# Voicecard-SVF-v0_7.net
KiCad netlist of a schematic drawn in EAGLE
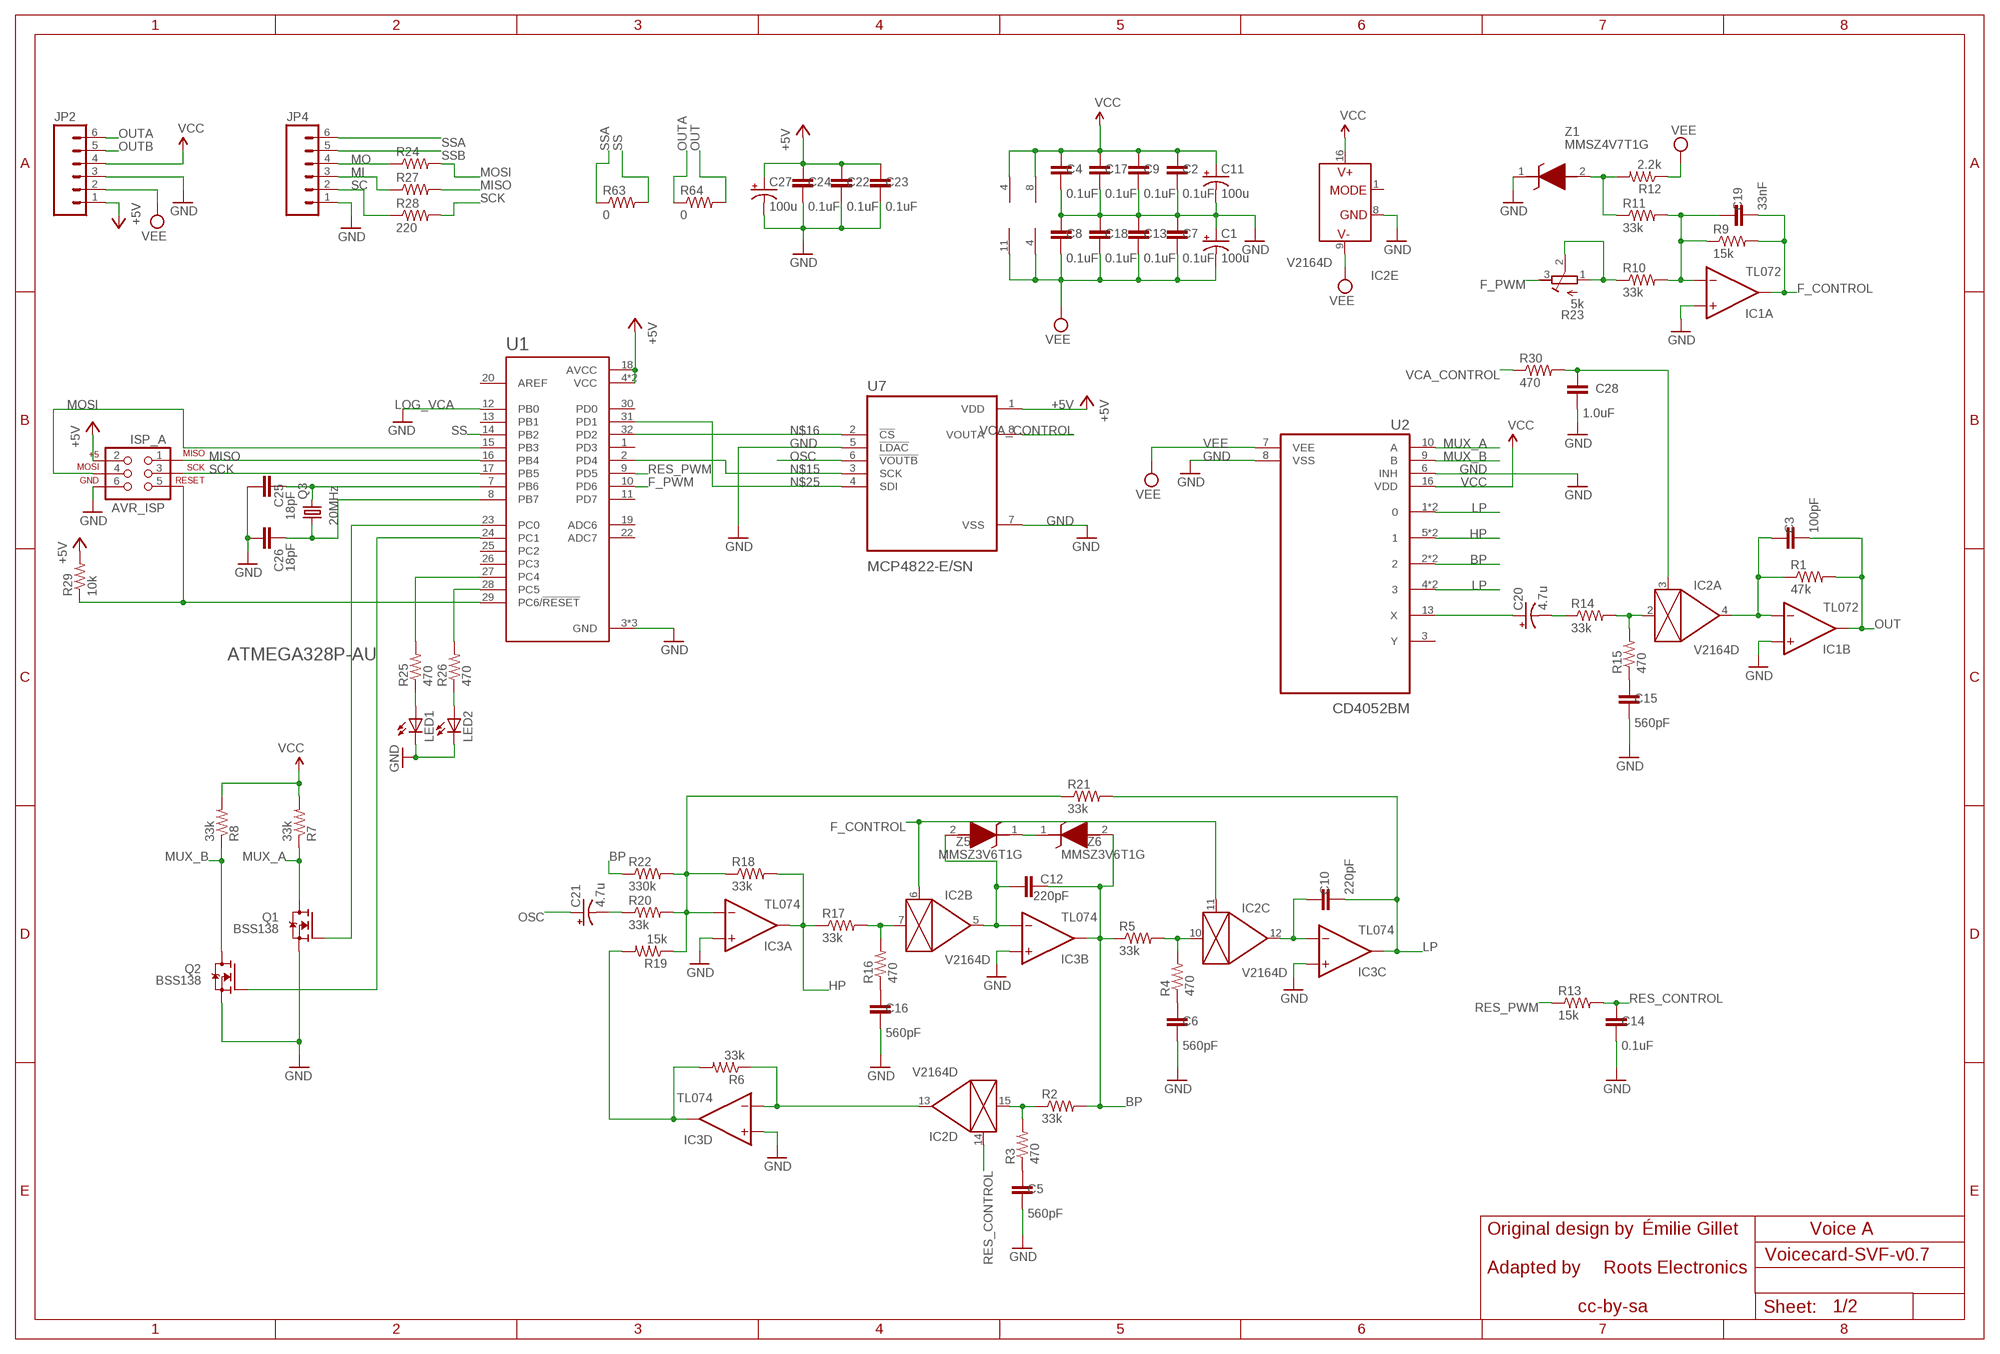
[diagram p0: schematic, sheet 1]
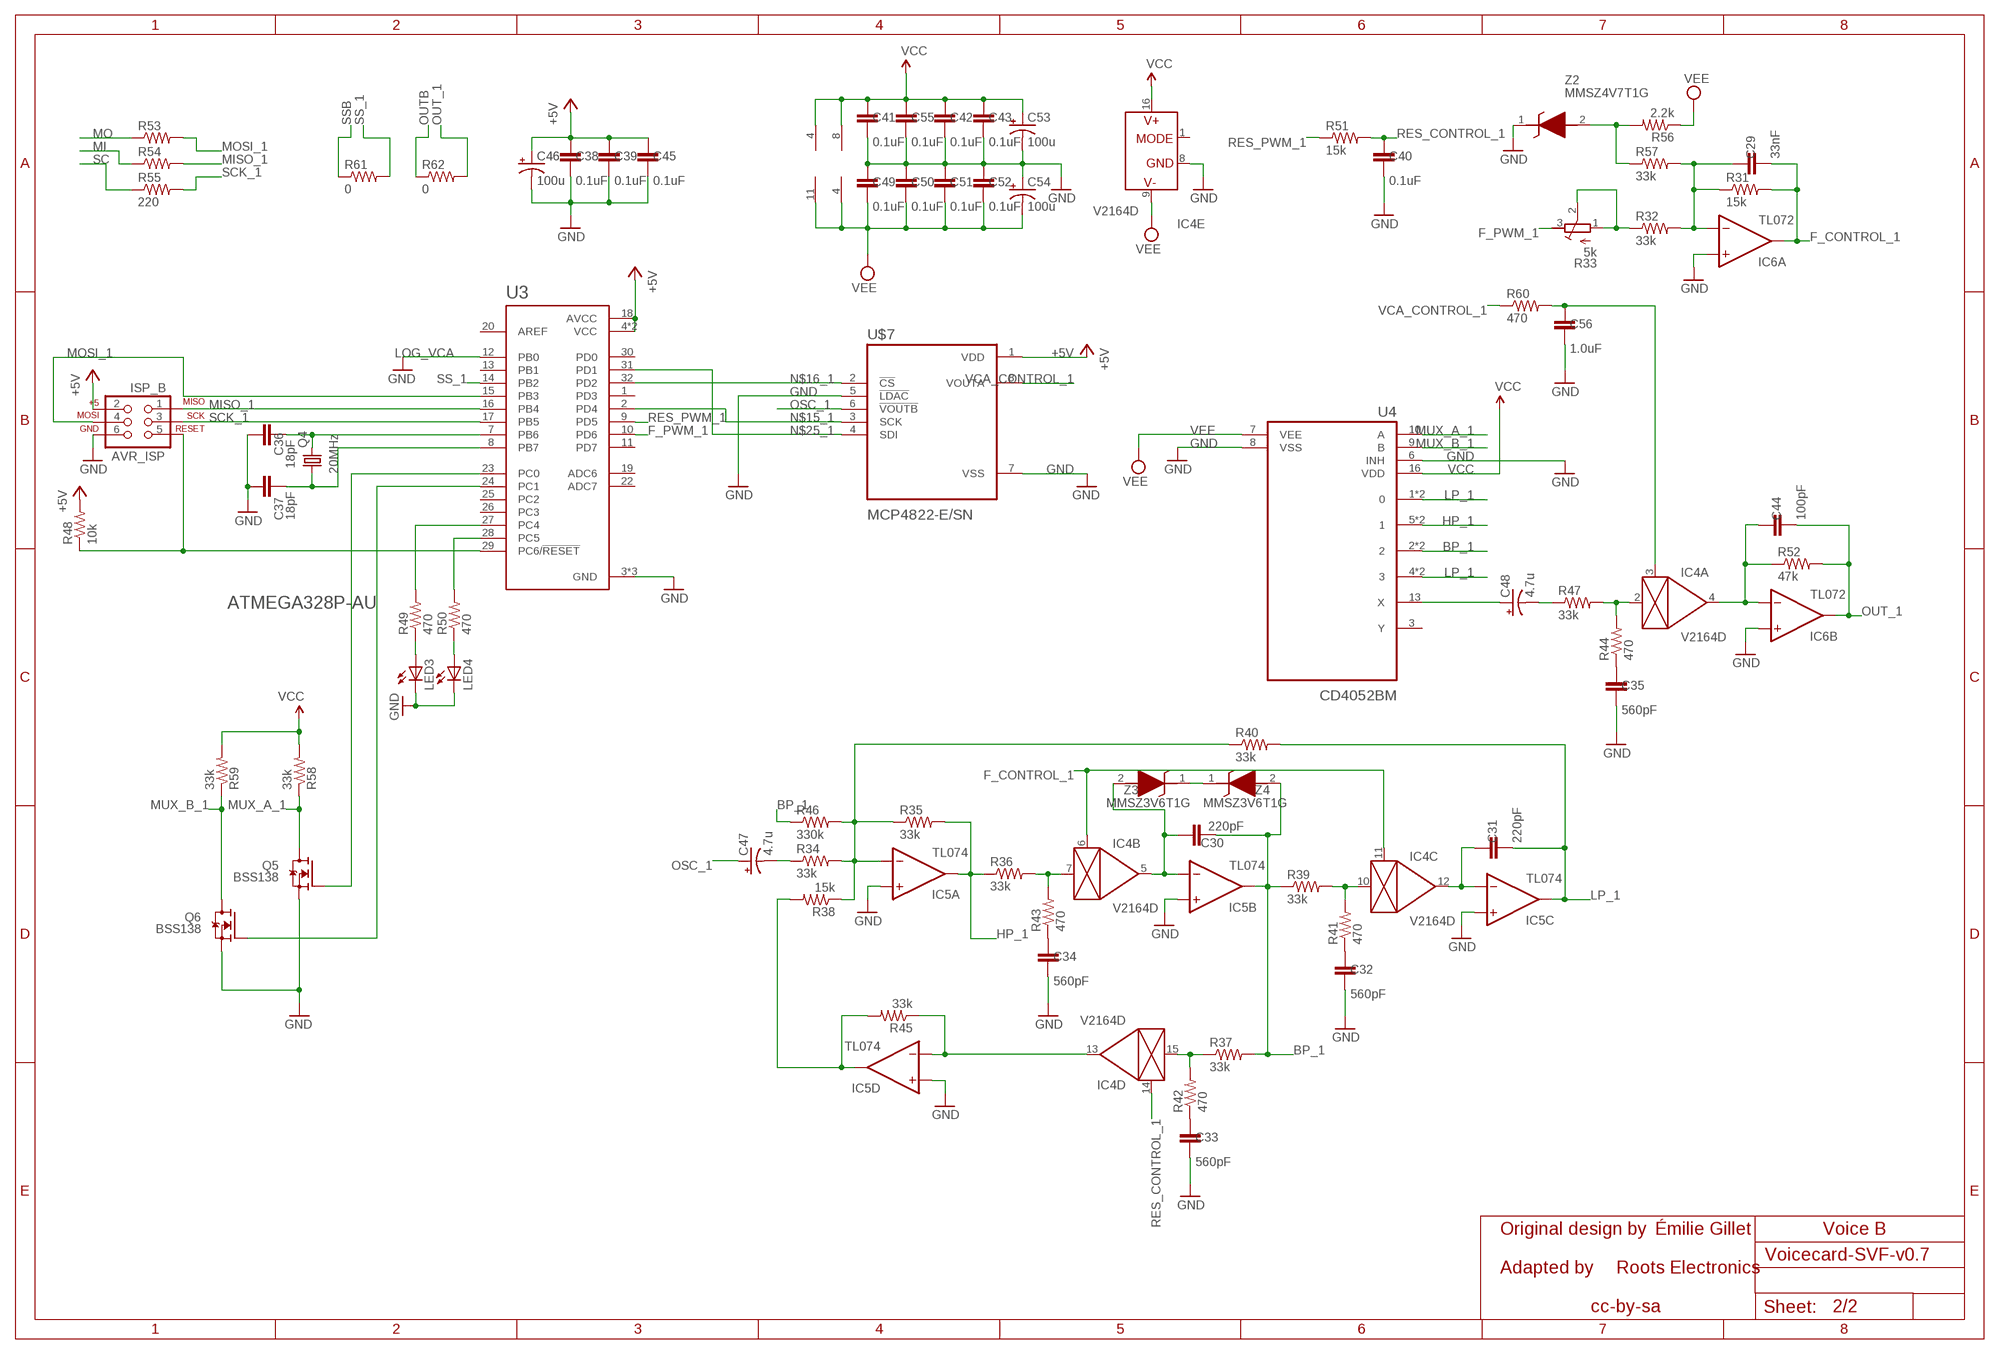
[diagram p1: schematic, sheet 2]

(export (version "E")
  (design (tool "Eeschema 10.0.6"))
  (components
    (comp (ref "C29")
      (value "33nF")
      (footprint "eagle-import:0603")
      (libsource (lib "eagle-import") (part "33NF-0603-50V-10%"))
    )
    (comp (ref "C30")
      (value "220pF")
      (footprint "eagle-import:0603")
      (libsource (lib "eagle-import") (part "270PF-0603-50V-5%"))
    )
    (comp (ref "C31")
      (value "220pF")
      (footprint "eagle-import:0603")
      (libsource (lib "eagle-import") (part "270PF-0603-50V-5%"))
    )
    (comp (ref "C32")
      (value "560pF")
      (footprint "eagle-import:0603")
      (libsource (lib "eagle-import") (part "560PF-0603-50V-5%"))
    )
    (comp (ref "C33")
      (value "560pF")
      (footprint "eagle-import:0603")
      (libsource (lib "eagle-import") (part "560PF-0603-50V-5%"))
    )
    (comp (ref "C34")
      (value "560pF")
      (footprint "eagle-import:0603")
      (libsource (lib "eagle-import") (part "560PF-0603-50V-5%"))
    )
    (comp (ref "C35")
      (value "560pF")
      (footprint "eagle-import:0603")
      (libsource (lib "eagle-import") (part "560PF-0603-50V-5%"))
    )
    (comp (ref "C36")
      (value "18pF")
      (footprint "eagle-import:0603")
      (libsource (lib "eagle-import") (part "18PF-0603-50V-5%"))
    )
    (comp (ref "C37")
      (value "18pF")
      (footprint "eagle-import:0603")
      (libsource (lib "eagle-import") (part "18PF-0603-50V-5%"))
    )
    (comp (ref "C38")
      (value "0.1uF")
      (footprint "eagle-import:0603")
      (libsource (lib "eagle-import") (part "0.1UF-0603-25V-5%"))
    )
    (comp (ref "C39")
      (value "0.1uF")
      (footprint "eagle-import:0603")
      (libsource (lib "eagle-import") (part "0.1UF-0603-25V-5%"))
    )
    (comp (ref "C40")
      (value "0.1uF")
      (footprint "eagle-import:0603")
      (libsource (lib "eagle-import") (part "0.1UF-0603-25V-5%"))
    )
    (comp (ref "C41")
      (value "0.1uF")
      (footprint "eagle-import:0603")
      (libsource (lib "eagle-import") (part "0.1UF-0603-25V-5%"))
    )
    (comp (ref "C42")
      (value "0.1uF")
      (footprint "eagle-import:0603")
      (libsource (lib "eagle-import") (part "0.1UF-0603-25V-5%"))
    )
    (comp (ref "C43")
      (value "0.1uF")
      (footprint "eagle-import:0603")
      (libsource (lib "eagle-import") (part "0.1UF-0603-25V-5%"))
    )
    (comp (ref "C44")
      (value "100pF")
      (footprint "eagle-import:0603")
      (libsource (lib "eagle-import") (part "100PF-0603-50V-5%"))
    )
    (comp (ref "C45")
      (value "0.1uF")
      (footprint "eagle-import:0603")
      (libsource (lib "eagle-import") (part "0.1UF-0603-25V-5%"))
    )
    (comp (ref "C46")
      (value "100u")
      (footprint "eagle-import:PANASONIC_C")
      (libsource (lib "eagle-import") (part "CPOL-USC"))
    )
    (comp (ref "C47")
      (value "4.7u")
      (footprint "eagle-import:PANASONIC_A")
      (libsource (lib "eagle-import") (part "CPOL-USA"))
    )
    (comp (ref "C48")
      (value "4.7u")
      (footprint "eagle-import:PANASONIC_A")
      (libsource (lib "eagle-import") (part "CPOL-USA"))
    )
    (comp (ref "C49")
      (value "0.1uF")
      (footprint "eagle-import:0603")
      (libsource (lib "eagle-import") (part "0.1UF-0603-25V-5%"))
    )
    (comp (ref "C50")
      (value "0.1uF")
      (footprint "eagle-import:0603")
      (libsource (lib "eagle-import") (part "0.1UF-0603-25V-5%"))
    )
    (comp (ref "C51")
      (value "0.1uF")
      (footprint "eagle-import:0603")
      (libsource (lib "eagle-import") (part "0.1UF-0603-25V-5%"))
    )
    (comp (ref "C52")
      (value "0.1uF")
      (footprint "eagle-import:0603")
      (libsource (lib "eagle-import") (part "0.1UF-0603-25V-5%"))
    )
    (comp (ref "C53")
      (value "100u")
      (footprint "eagle-import:PANASONIC_C")
      (libsource (lib "eagle-import") (part "CPOL-USC"))
    )
    (comp (ref "C54")
      (value "100u")
      (footprint "eagle-import:PANASONIC_C")
      (libsource (lib "eagle-import") (part "CPOL-USC"))
    )
    (comp (ref "C55")
      (value "0.1uF")
      (footprint "eagle-import:0603")
      (libsource (lib "eagle-import") (part "0.1UF-0603-25V-5%"))
    )
    (comp (ref "C56")
      (value "1.0uF")
      (footprint "eagle-import:0603")
      (libsource (lib "eagle-import") (part "1.0UF-0603-16V-10%"))
    )
    (comp (ref "IC4")
      (value "V2164D")
      (footprint "eagle-import:SOIC16N")
      (libsource (lib "eagle-import") (part "SSM2164S"))
    )
    (comp (ref "IC5")
      (value "TL074")
      (footprint "eagle-import:SO14")
      (libsource (lib "eagle-import") (part "TL074_SMD"))
    )
    (comp (ref "IC6")
      (value "TL072")
      (footprint "eagle-import:SO08")
      (libsource (lib "eagle-import") (part "TL072_SMD"))
    )
    (comp (ref "ISP_B")
      (value "AVR_ISP")
      (footprint "eagle-import:2X3")
      (libsource (lib "eagle-import") (part "AVR_SPI_PRG_6PTH"))
    )
    (comp (ref "LED3")
      (value "LED3MM")
      (footprint "eagle-import:LED3MM")
      (libsource (lib "eagle-import") (part "LED3MM"))
    )
    (comp (ref "LED4")
      (value "LED3MM")
      (footprint "eagle-import:LED3MM")
      (libsource (lib "eagle-import") (part "LED3MM"))
    )
    (comp (ref "Q4")
      (value "20MHz")
      (footprint "eagle-import:HC49UP")
      (libsource (lib "eagle-import") (part "CRYSTALHC49UP"))
    )
    (comp (ref "Q5")
      (value "BSS138")
      (footprint "eagle-import:SOT95P240X111-3N")
      (fields (field (name "MF") "ON Semiconductor"))
      (libsource (lib "eagle-import") (part "BSS138"))
    )
    (comp (ref "Q6")
      (value "BSS138")
      (footprint "eagle-import:SOT95P240X111-3N")
      (fields (field (name "MF") "ON Semiconductor"))
      (libsource (lib "eagle-import") (part "BSS138"))
    )
    (comp (ref "R31")
      (value "15k")
      (footprint "eagle-import:0603")
      (libsource (lib "eagle-import") (part "15KOHM-0603-1/10W-1%"))
    )
    (comp (ref "R32")
      (value "33k")
      (footprint "eagle-import:0603")
      (libsource (lib "eagle-import") (part "33KOHM-0603-1/10W-1%"))
    )
    (comp (ref "R33")
      (value "5k")
      (footprint "eagle-import:RTRIM3296P")
      (libsource (lib "eagle-import") (part "R-TRIMM3296P"))
    )
    (comp (ref "R34")
      (value "33k")
      (footprint "eagle-import:0603")
      (libsource (lib "eagle-import") (part "33KOHM-0603-1/10W-1%"))
    )
    (comp (ref "R35")
      (value "33k")
      (footprint "eagle-import:0603")
      (libsource (lib "eagle-import") (part "33KOHM-0603-1/10W-1%"))
    )
    (comp (ref "R36")
      (value "33k")
      (footprint "eagle-import:0603")
      (libsource (lib "eagle-import") (part "33KOHM-0603-1/10W-1%"))
    )
    (comp (ref "R37")
      (value "33k")
      (footprint "eagle-import:0603")
      (libsource (lib "eagle-import") (part "33KOHM-0603-1/10W-1%"))
    )
    (comp (ref "R38")
      (value "15k")
      (footprint "eagle-import:0603")
      (libsource (lib "eagle-import") (part "15KOHM-0603-1/10W-1%"))
    )
    (comp (ref "R39")
      (value "33k")
      (footprint "eagle-import:0603")
      (libsource (lib "eagle-import") (part "33KOHM-0603-1/10W-1%"))
    )
    (comp (ref "R40")
      (value "33k")
      (footprint "eagle-import:0603")
      (libsource (lib "eagle-import") (part "33KOHM-0603-1/10W-1%"))
    )
    (comp (ref "R41")
      (value "470")
      (footprint "eagle-import:0603")
      (libsource (lib "eagle-import") (part "470OHM-0603-1/10W-1%"))
    )
    (comp (ref "R42")
      (value "470")
      (footprint "eagle-import:0603")
      (libsource (lib "eagle-import") (part "470OHM-0603-1/10W-1%"))
    )
    (comp (ref "R43")
      (value "470")
      (footprint "eagle-import:0603")
      (libsource (lib "eagle-import") (part "470OHM-0603-1/10W-1%"))
    )
    (comp (ref "R44")
      (value "470")
      (footprint "eagle-import:0603")
      (libsource (lib "eagle-import") (part "470OHM-0603-1/10W-1%"))
    )
    (comp (ref "R45")
      (value "33k")
      (footprint "eagle-import:0603")
      (libsource (lib "eagle-import") (part "33KOHM-0603-1/10W-1%"))
    )
    (comp (ref "R46")
      (value "330k")
      (footprint "eagle-import:0603")
      (libsource (lib "eagle-import") (part "330KOHM-0603-1/10W-1%"))
    )
    (comp (ref "R47")
      (value "33k")
      (footprint "eagle-import:0603")
      (libsource (lib "eagle-import") (part "33KOHM-0603-1/10W-1%"))
    )
    (comp (ref "R48")
      (value "10k")
      (footprint "eagle-import:0603")
      (libsource (lib "eagle-import") (part "10KOHM-0603-1/10W-1%"))
    )
    (comp (ref "R49")
      (value "470")
      (footprint "eagle-import:0603")
      (libsource (lib "eagle-import") (part "470OHM-0603-1/10W-1%"))
    )
    (comp (ref "R50")
      (value "470")
      (footprint "eagle-import:0603")
      (libsource (lib "eagle-import") (part "470OHM-0603-1/10W-1%"))
    )
    (comp (ref "R51")
      (value "15k")
      (footprint "eagle-import:0603")
      (libsource (lib "eagle-import") (part "15KOHM-0603-1/10W-1%"))
    )
    (comp (ref "R52")
      (value "47k")
      (footprint "eagle-import:0603")
      (libsource (lib "eagle-import") (part "47KOHM-0603-1/10W-1%"))
    )
    (comp (ref "R53")
      (value "220")
      (footprint "eagle-import:0603")
      (libsource (lib "eagle-import") (part "220OHM-0603-1/10W-1%"))
    )
    (comp (ref "R54")
      (value "220")
      (footprint "eagle-import:0603")
      (libsource (lib "eagle-import") (part "220OHM-0603-1/10W-1%"))
    )
    (comp (ref "R55")
      (value "220")
      (footprint "eagle-import:0603")
      (libsource (lib "eagle-import") (part "220OHM-0603-1/10W-1%"))
    )
    (comp (ref "R56")
      (value "2.2k")
      (footprint "eagle-import:0603")
      (libsource (lib "eagle-import") (part "2.2KOHM-0603-1/10W-1%"))
    )
    (comp (ref "R57")
      (value "33k")
      (footprint "eagle-import:0603")
      (libsource (lib "eagle-import") (part "33KOHM-0603-1/10W-1%"))
    )
    (comp (ref "R58")
      (value "33k")
      (footprint "eagle-import:0603")
      (libsource (lib "eagle-import") (part "33KOHM-0603-1/10W-1%"))
    )
    (comp (ref "R59")
      (value "33k")
      (footprint "eagle-import:0603")
      (libsource (lib "eagle-import") (part "33KOHM-0603-1/10W-1%"))
    )
    (comp (ref "R60")
      (value "470")
      (footprint "eagle-import:0603")
      (libsource (lib "eagle-import") (part "470OHM-0603-1/10W-1%"))
    )
    (comp (ref "R61")
      (value "0")
      (footprint "eagle-import:0603")
      (libsource (lib "eagle-import") (part "220OHM-0603-1/10W-1%"))
    )
    (comp (ref "R62")
      (value "0")
      (footprint "eagle-import:0603")
      (libsource (lib "eagle-import") (part "220OHM-0603-1/10W-1%"))
    )
    (comp (ref "U$7")
      (value "MCP4822-E/SN")
      (footprint "eagle-import:SOIC127P599X175-8N")
      (fields (field (name "MF") "Microchip"))
      (libsource (lib "eagle-import") (part "MCP4822-E/SN"))
    )
    (comp (ref "U3")
      (value "ATMEGA328P-AU")
      (footprint "eagle-import:QFP80P900X900X120-32N")
      (fields (field (name "MF") "Microchip Technology"))
      (libsource (lib "eagle-import") (part "ATMEGA328P-AU"))
    )
    (comp (ref "U4")
      (value "CD4052BM")
      (footprint "eagle-import:SOIC127P600X175-16N")
      (fields (field (name "MF") "Texas Instruments"))
      (libsource (lib "eagle-import") (part "CD4052BM"))
    )
    (comp (ref "Z2")
      (value "MMSZ4V7T1G")
      (footprint "eagle-import:SOD3716X135N")
      (fields (field (name "MOUSER_PART_NUMBER") "863-MMSZ4V7T1G"))
      (libsource (lib "eagle-import") (part "MMSZ4V7T1G"))
    )
    (comp (ref "Z3")
      (value "MMSZ3V6T1G")
      (footprint "eagle-import:SOD3716X135N")
      (fields (field (name "MOUSER_PART_NUMBER") "863-MMSZ3V6T1G"))
      (libsource (lib "eagle-import") (part "MMSZ3V6T1G"))
    )
    (comp (ref "Z4")
      (value "MMSZ3V6T1G")
      (footprint "eagle-import:SOD3716X135N")
      (fields (field (name "MOUSER_PART_NUMBER") "863-MMSZ3V6T1G"))
      (libsource (lib "eagle-import") (part "MMSZ3V6T1G"))
    )
    (comp (ref "C1")
      (value "100u")
      (footprint "eagle-import:PANASONIC_C")
      (libsource (lib "eagle-import") (part "CPOL-USC"))
    )
    (comp (ref "C2")
      (value "0.1uF")
      (footprint "eagle-import:0603")
      (libsource (lib "eagle-import") (part "0.1UF-0603-25V-5%"))
    )
    (comp (ref "C3")
      (value "100pF")
      (footprint "eagle-import:0603")
      (libsource (lib "eagle-import") (part "100PF-0603-50V-5%"))
    )
    (comp (ref "C4")
      (value "0.1uF")
      (footprint "eagle-import:0603")
      (libsource (lib "eagle-import") (part "0.1UF-0603-25V-5%"))
    )
    (comp (ref "C5")
      (value "560pF")
      (footprint "eagle-import:0603")
      (libsource (lib "eagle-import") (part "560PF-0603-50V-5%"))
    )
    (comp (ref "C6")
      (value "560pF")
      (footprint "eagle-import:0603")
      (libsource (lib "eagle-import") (part "560PF-0603-50V-5%"))
    )
    (comp (ref "C7")
      (value "0.1uF")
      (footprint "eagle-import:0603")
      (libsource (lib "eagle-import") (part "0.1UF-0603-25V-5%"))
    )
    (comp (ref "C8")
      (value "0.1uF")
      (footprint "eagle-import:0603")
      (libsource (lib "eagle-import") (part "0.1UF-0603-25V-5%"))
    )
    (comp (ref "C9")
      (value "0.1uF")
      (footprint "eagle-import:0603")
      (libsource (lib "eagle-import") (part "0.1UF-0603-25V-5%"))
    )
    (comp (ref "C10")
      (value "220pF")
      (footprint "eagle-import:0603")
      (libsource (lib "eagle-import") (part "270PF-0603-50V-5%"))
    )
    (comp (ref "C11")
      (value "100u")
      (footprint "eagle-import:PANASONIC_C")
      (libsource (lib "eagle-import") (part "CPOL-USC"))
    )
    (comp (ref "C12")
      (value "220pF")
      (footprint "eagle-import:0603")
      (libsource (lib "eagle-import") (part "270PF-0603-50V-5%"))
    )
    (comp (ref "C13")
      (value "0.1uF")
      (footprint "eagle-import:0603")
      (libsource (lib "eagle-import") (part "0.1UF-0603-25V-5%"))
    )
    (comp (ref "C14")
      (value "0.1uF")
      (footprint "eagle-import:0603")
      (libsource (lib "eagle-import") (part "0.1UF-0603-25V-5%"))
    )
    (comp (ref "C15")
      (value "560pF")
      (footprint "eagle-import:0603")
      (libsource (lib "eagle-import") (part "560PF-0603-50V-5%"))
    )
    (comp (ref "C16")
      (value "560pF")
      (footprint "eagle-import:0603")
      (libsource (lib "eagle-import") (part "560PF-0603-50V-5%"))
    )
    (comp (ref "C17")
      (value "0.1uF")
      (footprint "eagle-import:0603")
      (libsource (lib "eagle-import") (part "0.1UF-0603-25V-5%"))
    )
    (comp (ref "C18")
      (value "0.1uF")
      (footprint "eagle-import:0603")
      (libsource (lib "eagle-import") (part "0.1UF-0603-25V-5%"))
    )
    (comp (ref "C19")
      (value "33nF")
      (footprint "eagle-import:0603")
      (libsource (lib "eagle-import") (part "33NF-0603-50V-10%"))
    )
    (comp (ref "C20")
      (value "4.7u")
      (footprint "eagle-import:PANASONIC_A")
      (libsource (lib "eagle-import") (part "CPOL-USA"))
    )
    (comp (ref "C21")
      (value "4.7u")
      (footprint "eagle-import:PANASONIC_A")
      (libsource (lib "eagle-import") (part "CPOL-USA"))
    )
    (comp (ref "C22")
      (value "0.1uF")
      (footprint "eagle-import:0603")
      (libsource (lib "eagle-import") (part "0.1UF-0603-25V-5%"))
    )
    (comp (ref "C23")
      (value "0.1uF")
      (footprint "eagle-import:0603")
      (libsource (lib "eagle-import") (part "0.1UF-0603-25V-5%"))
    )
    (comp (ref "C24")
      (value "0.1uF")
      (footprint "eagle-import:0603")
      (libsource (lib "eagle-import") (part "0.1UF-0603-25V-5%"))
    )
    (comp (ref "C25")
      (value "18pF")
      (footprint "eagle-import:0603")
      (libsource (lib "eagle-import") (part "18PF-0603-50V-5%"))
    )
    (comp (ref "C26")
      (value "18pF")
      (footprint "eagle-import:0603")
      (libsource (lib "eagle-import") (part "18PF-0603-50V-5%"))
    )
    (comp (ref "C27")
      (value "100u")
      (footprint "eagle-import:PANASONIC_C")
      (libsource (lib "eagle-import") (part "CPOL-USC"))
    )
    (comp (ref "C28")
      (value "1.0uF")
      (footprint "eagle-import:0603")
      (libsource (lib "eagle-import") (part "1.0UF-0603-16V-10%"))
    )
    (comp (ref "IC1")
      (value "TL072")
      (footprint "eagle-import:SO08")
      (libsource (lib "eagle-import") (part "TL072_SMD"))
    )
    (comp (ref "IC2")
      (value "V2164D")
      (footprint "eagle-import:SOIC16N")
      (libsource (lib "eagle-import") (part "SSM2164S"))
    )
    (comp (ref "IC3")
      (value "TL074")
      (footprint "eagle-import:SO14")
      (libsource (lib "eagle-import") (part "TL074_SMD"))
    )
    (comp (ref "ISP_A")
      (value "AVR_ISP")
      (footprint "eagle-import:2X3")
      (libsource (lib "eagle-import") (part "AVR_SPI_PRG_6PTH"))
    )
    (comp (ref "JP2")
      (value "M06SIP")
      (footprint "eagle-import:1X06")
      (libsource (lib "eagle-import") (part "M06SIP"))
    )
    (comp (ref "JP4")
      (value "M06SIP")
      (footprint "eagle-import:1X06")
      (libsource (lib "eagle-import") (part "M06SIP"))
    )
    (comp (ref "LED1")
      (value "LED3MM")
      (footprint "eagle-import:LED3MM")
      (libsource (lib "eagle-import") (part "LED3MM"))
    )
    (comp (ref "LED2")
      (value "LED3MM")
      (footprint "eagle-import:LED3MM")
      (libsource (lib "eagle-import") (part "LED3MM"))
    )
    (comp (ref "Q1")
      (value "BSS138")
      (footprint "eagle-import:SOT95P240X111-3N")
      (fields (field (name "MF") "ON Semiconductor"))
      (libsource (lib "eagle-import") (part "BSS138"))
    )
    (comp (ref "Q2")
      (value "BSS138")
      (footprint "eagle-import:SOT95P240X111-3N")
      (fields (field (name "MF") "ON Semiconductor"))
      (libsource (lib "eagle-import") (part "BSS138"))
    )
    (comp (ref "Q3")
      (value "20MHz")
      (footprint "eagle-import:HC49UP")
      (libsource (lib "eagle-import") (part "CRYSTALHC49UP"))
    )
    (comp (ref "R1")
      (value "47k")
      (footprint "eagle-import:0603")
      (libsource (lib "eagle-import") (part "47KOHM-0603-1/10W-1%"))
    )
    (comp (ref "R2")
      (value "33k")
      (footprint "eagle-import:0603")
      (libsource (lib "eagle-import") (part "33KOHM-0603-1/10W-1%"))
    )
    (comp (ref "R3")
      (value "470")
      (footprint "eagle-import:0603")
      (libsource (lib "eagle-import") (part "470OHM-0603-1/10W-1%"))
    )
    (comp (ref "R4")
      (value "470")
      (footprint "eagle-import:0603")
      (libsource (lib "eagle-import") (part "470OHM-0603-1/10W-1%"))
    )
    (comp (ref "R5")
      (value "33k")
      (footprint "eagle-import:0603")
      (libsource (lib "eagle-import") (part "33KOHM-0603-1/10W-1%"))
    )
    (comp (ref "R6")
      (value "33k")
      (footprint "eagle-import:0603")
      (libsource (lib "eagle-import") (part "33KOHM-0603-1/10W-1%"))
    )
    (comp (ref "R7")
      (value "33k")
      (footprint "eagle-import:0603")
      (libsource (lib "eagle-import") (part "33KOHM-0603-1/10W-1%"))
    )
    (comp (ref "R8")
      (value "33k")
      (footprint "eagle-import:0603")
      (libsource (lib "eagle-import") (part "33KOHM-0603-1/10W-1%"))
    )
    (comp (ref "R9")
      (value "15k")
      (footprint "eagle-import:0603")
      (libsource (lib "eagle-import") (part "15KOHM-0603-1/10W-1%"))
    )
    (comp (ref "R10")
      (value "33k")
      (footprint "eagle-import:0603")
      (libsource (lib "eagle-import") (part "33KOHM-0603-1/10W-1%"))
    )
    (comp (ref "R11")
      (value "33k")
      (footprint "eagle-import:0603")
      (libsource (lib "eagle-import") (part "33KOHM-0603-1/10W-1%"))
    )
    (comp (ref "R12")
      (value "2.2k")
      (footprint "eagle-import:0603")
      (libsource (lib "eagle-import") (part "2.2KOHM-0603-1/10W-1%"))
    )
    (comp (ref "R13")
      (value "15k")
      (footprint "eagle-import:0603")
      (libsource (lib "eagle-import") (part "15KOHM-0603-1/10W-1%"))
    )
    (comp (ref "R14")
      (value "33k")
      (footprint "eagle-import:0603")
      (libsource (lib "eagle-import") (part "33KOHM-0603-1/10W-1%"))
    )
    (comp (ref "R15")
      (value "470")
      (footprint "eagle-import:0603")
      (libsource (lib "eagle-import") (part "470OHM-0603-1/10W-1%"))
    )
    (comp (ref "R16")
      (value "470")
      (footprint "eagle-import:0603")
      (libsource (lib "eagle-import") (part "470OHM-0603-1/10W-1%"))
    )
    (comp (ref "R17")
      (value "33k")
      (footprint "eagle-import:0603")
      (libsource (lib "eagle-import") (part "33KOHM-0603-1/10W-1%"))
    )
    (comp (ref "R18")
      (value "33k")
      (footprint "eagle-import:0603")
      (libsource (lib "eagle-import") (part "33KOHM-0603-1/10W-1%"))
    )
    (comp (ref "R19")
      (value "15k")
      (footprint "eagle-import:0603")
      (libsource (lib "eagle-import") (part "15KOHM-0603-1/10W-1%"))
    )
    (comp (ref "R20")
      (value "33k")
      (footprint "eagle-import:0603")
      (libsource (lib "eagle-import") (part "33KOHM-0603-1/10W-1%"))
    )
    (comp (ref "R21")
      (value "33k")
      (footprint "eagle-import:0603")
      (libsource (lib "eagle-import") (part "33KOHM-0603-1/10W-1%"))
    )
    (comp (ref "R22")
      (value "330k")
      (footprint "eagle-import:0603")
      (libsource (lib "eagle-import") (part "330KOHM-0603-1/10W-1%"))
    )
    (comp (ref "R23")
      (value "5k")
      (footprint "eagle-import:RTRIM3296P")
      (libsource (lib "eagle-import") (part "R-TRIMM3296P"))
    )
    (comp (ref "R24")
      (value "220")
      (footprint "eagle-import:0603")
      (libsource (lib "eagle-import") (part "220OHM-0603-1/10W-1%"))
    )
    (comp (ref "R25")
      (value "470")
      (footprint "eagle-import:0603")
      (libsource (lib "eagle-import") (part "470OHM-0603-1/10W-1%"))
    )
    (comp (ref "R26")
      (value "470")
      (footprint "eagle-import:0603")
      (libsource (lib "eagle-import") (part "470OHM-0603-1/10W-1%"))
    )
    (comp (ref "R27")
      (value "220")
      (footprint "eagle-import:0603")
      (libsource (lib "eagle-import") (part "220OHM-0603-1/10W-1%"))
    )
    (comp (ref "R28")
      (value "220")
      (footprint "eagle-import:0603")
      (libsource (lib "eagle-import") (part "220OHM-0603-1/10W-1%"))
    )
    (comp (ref "R29")
      (value "10k")
      (footprint "eagle-import:0603")
      (libsource (lib "eagle-import") (part "10KOHM-0603-1/10W-1%"))
    )
    (comp (ref "R30")
      (value "470")
      (footprint "eagle-import:0603")
      (libsource (lib "eagle-import") (part "470OHM-0603-1/10W-1%"))
    )
    (comp (ref "R63")
      (value "0")
      (footprint "eagle-import:0603")
      (libsource (lib "eagle-import") (part "220OHM-0603-1/10W-1%"))
    )
    (comp (ref "R64")
      (value "0")
      (footprint "eagle-import:0603")
      (libsource (lib "eagle-import") (part "220OHM-0603-1/10W-1%"))
    )
    (comp (ref "U1")
      (value "ATMEGA328P-AU")
      (footprint "eagle-import:QFP80P900X900X120-32N")
      (fields (field (name "MF") "Microchip Technology"))
      (libsource (lib "eagle-import") (part "ATMEGA328P-AU"))
    )
    (comp (ref "U2")
      (value "CD4052BM")
      (footprint "eagle-import:SOIC127P600X175-16N")
      (fields (field (name "MF") "Texas Instruments"))
      (libsource (lib "eagle-import") (part "CD4052BM"))
    )
    (comp (ref "U7")
      (value "MCP4822-E/SN")
      (footprint "eagle-import:SOIC127P599X175-8N")
      (fields (field (name "MF") "Microchip"))
      (libsource (lib "eagle-import") (part "MCP4822-E/SN"))
    )
    (comp (ref "Z1")
      (value "MMSZ4V7T1G")
      (footprint "eagle-import:SOD3716X135N")
      (fields (field (name "MOUSER_PART_NUMBER") "863-MMSZ4V7T1G"))
      (libsource (lib "eagle-import") (part "MMSZ4V7T1G"))
    )
    (comp (ref "Z5")
      (value "MMSZ3V6T1G")
      (footprint "eagle-import:SOD3716X135N")
      (fields (field (name "MOUSER_PART_NUMBER") "863-MMSZ3V6T1G"))
      (libsource (lib "eagle-import") (part "MMSZ3V6T1G"))
    )
    (comp (ref "Z6")
      (value "MMSZ3V6T1G")
      (footprint "eagle-import:SOD3716X135N")
      (fields (field (name "MOUSER_PART_NUMBER") "863-MMSZ3V6T1G"))
      (libsource (lib "eagle-import") (part "MMSZ3V6T1G"))
    )
  )
  (nets
    (net (code "1") (name "+5V") (class "Default")
      (node (ref "C22") (pin "1") (pinfunction "1_1") (pintype "passive"))
      (node (ref "C23") (pin "1") (pinfunction "1_1") (pintype "passive"))
      (node (ref "C24") (pin "1") (pinfunction "1_1") (pintype "passive"))
      (node (ref "C27") (pin "+") (pinfunction "+_+") (pintype "passive"))
      (node (ref "C38") (pin "1") (pinfunction "1_1") (pintype "passive"))
      (node (ref "C39") (pin "1") (pinfunction "1_1") (pintype "passive"))
      (node (ref "C45") (pin "1") (pinfunction "1_1") (pintype "passive"))
      (node (ref "C46") (pin "+") (pinfunction "+_+") (pintype "passive"))
      (node (ref "ISP_A") (pin "2") (pinfunction "2_2") (pintype "passive"))
      (node (ref "ISP_B") (pin "2") (pinfunction "2_2") (pintype "passive"))
      (node (ref "JP2") (pin "1") (pinfunction "1_1") (pintype "passive"))
      (node (ref "R29") (pin "2") (pinfunction "2_2") (pintype "passive"))
      (node (ref "R48") (pin "2") (pinfunction "2_2") (pintype "passive"))
      (node (ref "U$7") (pin "1") (pinfunction "VDD_1") (pintype "power_in"))
      (node (ref "U1") (pin "18") (pinfunction "AVCC_18") (pintype "power_in"))
      (node (ref "U1") (pin "4") (pinfunction "VCC_4") (pintype "power_in"))
      (node (ref "U1") (pin "6") (pinfunction "VCC_6") (pintype "power_in"))
      (node (ref "U3") (pin "18") (pinfunction "AVCC_18") (pintype "power_in"))
      (node (ref "U3") (pin "4") (pinfunction "VCC_4") (pintype "power_in"))
      (node (ref "U3") (pin "6") (pinfunction "VCC_6") (pintype "power_in"))
      (node (ref "U7") (pin "1") (pinfunction "VDD_1") (pintype "power_in"))
    )
    (net (code "2") (name "BP") (class "Default")
      (node (ref "C12") (pin "2") (pinfunction "2_2") (pintype "passive"))
      (node (ref "IC3") (pin "7") (pinfunction "OUT_7") (pintype "output"))
      (node (ref "R2") (pin "2") (pinfunction "2_2") (pintype "passive"))
      (node (ref "R22") (pin "1") (pinfunction "1_1") (pintype "passive"))
      (node (ref "R5") (pin "1") (pinfunction "1_1") (pintype "passive"))
      (node (ref "U2") (pin "15") (pinfunction "2_15") (pintype "bidirectional"))
      (node (ref "U2") (pin "2") (pinfunction "2_2") (pintype "bidirectional"))
      (node (ref "Z6") (pin "2") (pinfunction "A_2") (pintype "bidirectional"))
    )
    (net (code "3") (name "BP_1") (class "Default")
      (node (ref "C30") (pin "2") (pinfunction "2_2") (pintype "passive"))
      (node (ref "IC5") (pin "7") (pinfunction "OUT_7") (pintype "output"))
      (node (ref "R37") (pin "2") (pinfunction "2_2") (pintype "passive"))
      (node (ref "R39") (pin "1") (pinfunction "1_1") (pintype "passive"))
      (node (ref "R46") (pin "1") (pinfunction "1_1") (pintype "passive"))
      (node (ref "U4") (pin "15") (pinfunction "2_15") (pintype "bidirectional"))
      (node (ref "U4") (pin "2") (pinfunction "2_2") (pintype "bidirectional"))
      (node (ref "Z4") (pin "2") (pinfunction "A_2") (pintype "bidirectional"))
    )
    (net (code "4") (name "F_CONTROL") (class "Default")
      (node (ref "C19") (pin "2") (pinfunction "2_2") (pintype "passive"))
      (node (ref "IC1") (pin "1") (pinfunction "OUT_1") (pintype "output"))
      (node (ref "IC2") (pin "11") (pinfunction "CTRL_11") (pintype "input"))
      (node (ref "IC2") (pin "6") (pinfunction "CTRL_6") (pintype "input"))
      (node (ref "R9") (pin "2") (pinfunction "2_2") (pintype "passive"))
    )
    (net (code "5") (name "F_CONTROL_1") (class "Default")
      (node (ref "C29") (pin "2") (pinfunction "2_2") (pintype "passive"))
      (node (ref "IC4") (pin "11") (pinfunction "CTRL_11") (pintype "input"))
      (node (ref "IC4") (pin "6") (pinfunction "CTRL_6") (pintype "input"))
      (node (ref "IC6") (pin "1") (pinfunction "OUT_1") (pintype "output"))
      (node (ref "R31") (pin "2") (pinfunction "2_2") (pintype "passive"))
    )
    (net (code "6") (name "F_PWM") (class "Default")
      (node (ref "R23") (pin "3") (pinfunction "A_3") (pintype "passive"))
      (node (ref "U1") (pin "10") (pinfunction "PD6_10") (pintype "bidirectional"))
    )
    (net (code "7") (name "F_PWM_1") (class "Default")
      (node (ref "R33") (pin "3") (pinfunction "A_3") (pintype "passive"))
      (node (ref "U3") (pin "10") (pinfunction "PD6_10") (pintype "bidirectional"))
    )
    (net (code "8") (name "GND") (class "Default")
      (node (ref "C1") (pin "+") (pinfunction "+_+") (pintype "passive"))
      (node (ref "C11") (pin "-") (pinfunction "-_-") (pintype "passive"))
      (node (ref "C13") (pin "1") (pinfunction "1_1") (pintype "passive"))
      (node (ref "C14") (pin "2") (pinfunction "2_2") (pintype "passive"))
      (node (ref "C15") (pin "2") (pinfunction "2_2") (pintype "passive"))
      (node (ref "C16") (pin "2") (pinfunction "2_2") (pintype "passive"))
      (node (ref "C17") (pin "2") (pinfunction "2_2") (pintype "passive"))
      (node (ref "C18") (pin "1") (pinfunction "1_1") (pintype "passive"))
      (node (ref "C2") (pin "2") (pinfunction "2_2") (pintype "passive"))
      (node (ref "C22") (pin "2") (pinfunction "2_2") (pintype "passive"))
      (node (ref "C23") (pin "2") (pinfunction "2_2") (pintype "passive"))
      (node (ref "C24") (pin "2") (pinfunction "2_2") (pintype "passive"))
      (node (ref "C25") (pin "1") (pinfunction "1_1") (pintype "passive"))
      (node (ref "C26") (pin "1") (pinfunction "1_1") (pintype "passive"))
      (node (ref "C27") (pin "-") (pinfunction "-_-") (pintype "passive"))
      (node (ref "C28") (pin "2") (pinfunction "2_2") (pintype "passive"))
      (node (ref "C32") (pin "2") (pinfunction "2_2") (pintype "passive"))
      (node (ref "C33") (pin "2") (pinfunction "2_2") (pintype "passive"))
      (node (ref "C34") (pin "2") (pinfunction "2_2") (pintype "passive"))
      (node (ref "C35") (pin "2") (pinfunction "2_2") (pintype "passive"))
      (node (ref "C36") (pin "1") (pinfunction "1_1") (pintype "passive"))
      (node (ref "C37") (pin "1") (pinfunction "1_1") (pintype "passive"))
      (node (ref "C38") (pin "2") (pinfunction "2_2") (pintype "passive"))
      (node (ref "C39") (pin "2") (pinfunction "2_2") (pintype "passive"))
      (node (ref "C4") (pin "2") (pinfunction "2_2") (pintype "passive"))
      (node (ref "C40") (pin "2") (pinfunction "2_2") (pintype "passive"))
      (node (ref "C41") (pin "2") (pinfunction "2_2") (pintype "passive"))
      (node (ref "C42") (pin "2") (pinfunction "2_2") (pintype "passive"))
      (node (ref "C43") (pin "2") (pinfunction "2_2") (pintype "passive"))
      (node (ref "C45") (pin "2") (pinfunction "2_2") (pintype "passive"))
      (node (ref "C46") (pin "-") (pinfunction "-_-") (pintype "passive"))
      (node (ref "C49") (pin "1") (pinfunction "1_1") (pintype "passive"))
      (node (ref "C5") (pin "2") (pinfunction "2_2") (pintype "passive"))
      (node (ref "C50") (pin "1") (pinfunction "1_1") (pintype "passive"))
      (node (ref "C51") (pin "1") (pinfunction "1_1") (pintype "passive"))
      (node (ref "C52") (pin "1") (pinfunction "1_1") (pintype "passive"))
      (node (ref "C53") (pin "-") (pinfunction "-_-") (pintype "passive"))
      (node (ref "C54") (pin "+") (pinfunction "+_+") (pintype "passive"))
      (node (ref "C55") (pin "2") (pinfunction "2_2") (pintype "passive"))
      (node (ref "C56") (pin "2") (pinfunction "2_2") (pintype "passive"))
      (node (ref "C6") (pin "2") (pinfunction "2_2") (pintype "passive"))
      (node (ref "C7") (pin "1") (pinfunction "1_1") (pintype "passive"))
      (node (ref "C8") (pin "1") (pinfunction "1_1") (pintype "passive"))
      (node (ref "C9") (pin "2") (pinfunction "2_2") (pintype "passive"))
      (node (ref "IC1") (pin "3") (pinfunction "+IN_3") (pintype "input"))
      (node (ref "IC1") (pin "5") (pinfunction "+IN_5") (pintype "input"))
      (node (ref "IC2") (pin "8") (pinfunction "GND_8") (pintype "power_in"))
      (node (ref "IC3") (pin "10") (pinfunction "+IN_10") (pintype "input"))
      (node (ref "IC3") (pin "12") (pinfunction "+IN_12") (pintype "input"))
      (node (ref "IC3") (pin "3") (pinfunction "+IN_3") (pintype "input"))
      (node (ref "IC3") (pin "5") (pinfunction "+IN_5") (pintype "input"))
      (node (ref "IC4") (pin "8") (pinfunction "GND_8") (pintype "power_in"))
      (node (ref "IC5") (pin "10") (pinfunction "+IN_10") (pintype "input"))
      (node (ref "IC5") (pin "12") (pinfunction "+IN_12") (pintype "input"))
      (node (ref "IC5") (pin "3") (pinfunction "+IN_3") (pintype "input"))
      (node (ref "IC5") (pin "5") (pinfunction "+IN_5") (pintype "input"))
      (node (ref "IC6") (pin "3") (pinfunction "+IN_3") (pintype "input"))
      (node (ref "IC6") (pin "5") (pinfunction "+IN_5") (pintype "input"))
      (node (ref "ISP_A") (pin "6") (pinfunction "6_6") (pintype "passive"))
      (node (ref "ISP_B") (pin "6") (pinfunction "6_6") (pintype "passive"))
      (node (ref "JP2") (pin "3") (pinfunction "3_3") (pintype "passive"))
      (node (ref "JP4") (pin "1") (pinfunction "1_1") (pintype "passive"))
      (node (ref "LED1") (pin "K") (pinfunction "C_K") (pintype "passive"))
      (node (ref "LED2") (pin "K") (pinfunction "C_K") (pintype "passive"))
      (node (ref "LED3") (pin "K") (pinfunction "C_K") (pintype "passive"))
      (node (ref "LED4") (pin "K") (pinfunction "C_K") (pintype "passive"))
      (node (ref "Q1") (pin "2") (pinfunction "S_2") (pintype "passive"))
      (node (ref "Q2") (pin "2") (pinfunction "S_2") (pintype "passive"))
      (node (ref "Q5") (pin "2") (pinfunction "S_2") (pintype "passive"))
      (node (ref "Q6") (pin "2") (pinfunction "S_2") (pintype "passive"))
      (node (ref "U$7") (pin "5") (pinfunction "~{LDAC}_5") (pintype "input"))
      (node (ref "U$7") (pin "7") (pinfunction "VSS_7") (pintype "power_in"))
      (node (ref "U1") (pin "12") (pinfunction "PB0_12") (pintype "bidirectional"))
      (node (ref "U1") (pin "21") (pinfunction "GND_21") (pintype "power_in"))
      (node (ref "U1") (pin "3") (pinfunction "GND_3") (pintype "power_in"))
      (node (ref "U1") (pin "5") (pinfunction "GND_5") (pintype "power_in"))
      (node (ref "U2") (pin "6") (pinfunction "INH_6") (pintype "input"))
      (node (ref "U2") (pin "8") (pinfunction "VSS_8") (pintype "power_in"))
      (node (ref "U3") (pin "12") (pinfunction "PB0_12") (pintype "bidirectional"))
      (node (ref "U3") (pin "21") (pinfunction "GND_21") (pintype "power_in"))
      (node (ref "U3") (pin "3") (pinfunction "GND_3") (pintype "power_in"))
      (node (ref "U3") (pin "5") (pinfunction "GND_5") (pintype "power_in"))
      (node (ref "U4") (pin "6") (pinfunction "INH_6") (pintype "input"))
      (node (ref "U4") (pin "8") (pinfunction "VSS_8") (pintype "power_in"))
      (node (ref "U7") (pin "5") (pinfunction "~{LDAC}_5") (pintype "input"))
      (node (ref "U7") (pin "7") (pinfunction "VSS_7") (pintype "power_in"))
      (node (ref "Z1") (pin "1") (pinfunction "K_1") (pintype "bidirectional"))
      (node (ref "Z2") (pin "1") (pinfunction "K_1") (pintype "bidirectional"))
    )
    (net (code "9") (name "HP") (class "Default")
      (node (ref "IC3") (pin "1") (pinfunction "OUT_1") (pintype "output"))
      (node (ref "R17") (pin "1") (pinfunction "1_1") (pintype "passive"))
      (node (ref "R18") (pin "2") (pinfunction "2_2") (pintype "passive"))
      (node (ref "U2") (pin "14") (pinfunction "1_14") (pintype "bidirectional"))
      (node (ref "U2") (pin "5") (pinfunction "1_5") (pintype "bidirectional"))
    )
    (net (code "10") (name "HP_1") (class "Default")
      (node (ref "IC5") (pin "1") (pinfunction "OUT_1") (pintype "output"))
      (node (ref "R35") (pin "2") (pinfunction "2_2") (pintype "passive"))
      (node (ref "R36") (pin "1") (pinfunction "1_1") (pintype "passive"))
      (node (ref "U4") (pin "14") (pinfunction "1_14") (pintype "bidirectional"))
      (node (ref "U4") (pin "5") (pinfunction "1_5") (pintype "bidirectional"))
    )
    (net (code "11") (name "LP") (class "Default")
      (node (ref "C10") (pin "2") (pinfunction "2_2") (pintype "passive"))
      (node (ref "IC3") (pin "8") (pinfunction "OUT_8") (pintype "output"))
      (node (ref "R21") (pin "2") (pinfunction "2_2") (pintype "passive"))
      (node (ref "U2") (pin "1") (pinfunction "0_1") (pintype "bidirectional"))
      (node (ref "U2") (pin "11") (pinfunction "3_11") (pintype "bidirectional"))
      (node (ref "U2") (pin "12") (pinfunction "0_12") (pintype "bidirectional"))
      (node (ref "U2") (pin "4") (pinfunction "3_4") (pintype "bidirectional"))
    )
    (net (code "12") (name "LP_1") (class "Default")
      (node (ref "C31") (pin "2") (pinfunction "2_2") (pintype "passive"))
      (node (ref "IC5") (pin "8") (pinfunction "OUT_8") (pintype "output"))
      (node (ref "R40") (pin "2") (pinfunction "2_2") (pintype "passive"))
      (node (ref "U4") (pin "1") (pinfunction "0_1") (pintype "bidirectional"))
      (node (ref "U4") (pin "11") (pinfunction "3_11") (pintype "bidirectional"))
      (node (ref "U4") (pin "12") (pinfunction "0_12") (pintype "bidirectional"))
      (node (ref "U4") (pin "4") (pinfunction "3_4") (pintype "bidirectional"))
    )
    (net (code "13") (name "MI") (class "Default")
      (node (ref "JP4") (pin "3") (pinfunction "3_3") (pintype "passive"))
      (node (ref "R27") (pin "1") (pinfunction "1_1") (pintype "passive"))
      (node (ref "R54") (pin "1") (pinfunction "1_1") (pintype "passive"))
    )
    (net (code "14") (name "MISO") (class "Default")
      (node (ref "ISP_A") (pin "1") (pinfunction "1_1") (pintype "passive"))
      (node (ref "R27") (pin "2") (pinfunction "2_2") (pintype "passive"))
      (node (ref "U1") (pin "16") (pinfunction "PB4_16") (pintype "bidirectional"))
    )
    (net (code "15") (name "MISO_1") (class "Default")
      (node (ref "ISP_B") (pin "1") (pinfunction "1_1") (pintype "passive"))
      (node (ref "R54") (pin "2") (pinfunction "2_2") (pintype "passive"))
      (node (ref "U3") (pin "16") (pinfunction "PB4_16") (pintype "bidirectional"))
    )
    (net (code "16") (name "MO") (class "Default")
      (node (ref "JP4") (pin "4") (pinfunction "4_4") (pintype "passive"))
      (node (ref "R24") (pin "1") (pinfunction "1_1") (pintype "passive"))
      (node (ref "R53") (pin "1") (pinfunction "1_1") (pintype "passive"))
    )
    (net (code "17") (name "MOSI") (class "Default")
      (node (ref "ISP_A") (pin "4") (pinfunction "4_4") (pintype "passive"))
      (node (ref "R24") (pin "2") (pinfunction "2_2") (pintype "passive"))
      (node (ref "U1") (pin "15") (pinfunction "PB3_15") (pintype "bidirectional"))
    )
    (net (code "18") (name "MOSI_1") (class "Default")
      (node (ref "ISP_B") (pin "4") (pinfunction "4_4") (pintype "passive"))
      (node (ref "R53") (pin "2") (pinfunction "2_2") (pintype "passive"))
      (node (ref "U3") (pin "15") (pinfunction "PB3_15") (pintype "bidirectional"))
    )
    (net (code "19") (name "MUX_A") (class "Default")
      (node (ref "Q1") (pin "3") (pinfunction "D_3") (pintype "passive"))
      (node (ref "R7") (pin "1") (pinfunction "1_1") (pintype "passive"))
      (node (ref "U2") (pin "10") (pinfunction "A_10") (pintype "input"))
    )
    (net (code "20") (name "MUX_A_1") (class "Default")
      (node (ref "Q5") (pin "3") (pinfunction "D_3") (pintype "passive"))
      (node (ref "R58") (pin "1") (pinfunction "1_1") (pintype "passive"))
      (node (ref "U4") (pin "10") (pinfunction "A_10") (pintype "input"))
    )
    (net (code "21") (name "MUX_B") (class "Default")
      (node (ref "Q2") (pin "3") (pinfunction "D_3") (pintype "passive"))
      (node (ref "R8") (pin "1") (pinfunction "1_1") (pintype "passive"))
      (node (ref "U2") (pin "9") (pinfunction "B_9") (pintype "input"))
    )
    (net (code "22") (name "MUX_B_1") (class "Default")
      (node (ref "Q6") (pin "3") (pinfunction "D_3") (pintype "passive"))
      (node (ref "R59") (pin "1") (pinfunction "1_1") (pintype "passive"))
      (node (ref "U4") (pin "9") (pinfunction "B_9") (pintype "input"))
    )
    (net (code "23") (name "N$15") (class "Default")
      (node (ref "U1") (pin "2") (pinfunction "PD4_2") (pintype "bidirectional"))
      (node (ref "U7") (pin "3") (pinfunction "SCK_3") (pintype "input"))
    )
    (net (code "24") (name "N$15_1") (class "Default")
      (node (ref "U$7") (pin "3") (pinfunction "SCK_3") (pintype "input"))
      (node (ref "U3") (pin "2") (pinfunction "PD4_2") (pintype "bidirectional"))
    )
    (net (code "25") (name "N$16") (class "Default")
      (node (ref "U1") (pin "32") (pinfunction "PD2_32") (pintype "bidirectional"))
      (node (ref "U7") (pin "2") (pinfunction "~{CS}_2") (pintype "input"))
    )
    (net (code "26") (name "N$16_1") (class "Default")
      (node (ref "U$7") (pin "2") (pinfunction "~{CS}_2") (pintype "input"))
      (node (ref "U3") (pin "32") (pinfunction "PD2_32") (pintype "bidirectional"))
    )
    (net (code "27") (name "N$25") (class "Default")
      (node (ref "U1") (pin "31") (pinfunction "PD1_31") (pintype "bidirectional"))
      (node (ref "U7") (pin "4") (pinfunction "SDI_4") (pintype "input"))
    )
    (net (code "28") (name "N$25_1") (class "Default")
      (node (ref "U$7") (pin "4") (pinfunction "SDI_4") (pintype "input"))
      (node (ref "U3") (pin "31") (pinfunction "PD1_31") (pintype "bidirectional"))
    )
    (net (code "29") (name "Net-(C5-Pad1)") (class "Default")
      (node (ref "C5") (pin "1") (pinfunction "1_1") (pintype "passive"))
      (node (ref "R3") (pin "1") (pinfunction "1_1") (pintype "passive"))
    )
    (net (code "30") (name "Net-(C6-Pad1)") (class "Default")
      (node (ref "C6") (pin "1") (pinfunction "1_1") (pintype "passive"))
      (node (ref "R4") (pin "1") (pinfunction "1_1") (pintype "passive"))
    )
    (net (code "31") (name "Net-(C15-Pad1)") (class "Default")
      (node (ref "C15") (pin "1") (pinfunction "1_1") (pintype "passive"))
      (node (ref "R15") (pin "1") (pinfunction "1_1") (pintype "passive"))
    )
    (net (code "32") (name "Net-(C16-Pad1)") (class "Default")
      (node (ref "C16") (pin "1") (pinfunction "1_1") (pintype "passive"))
      (node (ref "R16") (pin "1") (pinfunction "1_1") (pintype "passive"))
    )
    (net (code "33") (name "Net-(C20-Pad-)") (class "Default")
      (node (ref "C20") (pin "-") (pinfunction "-_-") (pintype "passive"))
      (node (ref "R14") (pin "1") (pinfunction "1_1") (pintype "passive"))
    )
    (net (code "34") (name "Net-(C21-Pad-)") (class "Default")
      (node (ref "C21") (pin "-") (pinfunction "-_-") (pintype "passive"))
      (node (ref "R20") (pin "1") (pinfunction "1_1") (pintype "passive"))
    )
    (net (code "35") (name "Net-(C32-Pad1)") (class "Default")
      (node (ref "C32") (pin "1") (pinfunction "1_1") (pintype "passive"))
      (node (ref "R41") (pin "1") (pinfunction "1_1") (pintype "passive"))
    )
    (net (code "36") (name "Net-(C33-Pad1)") (class "Default")
      (node (ref "C33") (pin "1") (pinfunction "1_1") (pintype "passive"))
      (node (ref "R42") (pin "1") (pinfunction "1_1") (pintype "passive"))
    )
    (net (code "37") (name "Net-(C34-Pad1)") (class "Default")
      (node (ref "C34") (pin "1") (pinfunction "1_1") (pintype "passive"))
      (node (ref "R43") (pin "1") (pinfunction "1_1") (pintype "passive"))
    )
    (net (code "38") (name "Net-(C35-Pad1)") (class "Default")
      (node (ref "C35") (pin "1") (pinfunction "1_1") (pintype "passive"))
      (node (ref "R44") (pin "1") (pinfunction "1_1") (pintype "passive"))
    )
    (net (code "39") (name "Net-(C47-Pad-)") (class "Default")
      (node (ref "C47") (pin "-") (pinfunction "-_-") (pintype "passive"))
      (node (ref "R34") (pin "1") (pinfunction "1_1") (pintype "passive"))
    )
    (net (code "40") (name "Net-(C48-Pad-)") (class "Default")
      (node (ref "C48") (pin "-") (pinfunction "-_-") (pintype "passive"))
      (node (ref "R47") (pin "1") (pinfunction "1_1") (pintype "passive"))
    )
    (net (code "41") (name "Net-(IC1A--IN)") (class "Default")
      (node (ref "C19") (pin "1") (pinfunction "1_1") (pintype "passive"))
      (node (ref "IC1") (pin "2") (pinfunction "-IN_2") (pintype "input"))
      (node (ref "R10") (pin "2") (pinfunction "2_2") (pintype "passive"))
      (node (ref "R11") (pin "2") (pinfunction "2_2") (pintype "passive"))
      (node (ref "R9") (pin "1") (pinfunction "1_1") (pintype "passive"))
    )
    (net (code "42") (name "Net-(IC1B--IN)") (class "Default")
      (node (ref "C3") (pin "1") (pinfunction "1_1") (pintype "passive"))
      (node (ref "IC1") (pin "6") (pinfunction "-IN_6") (pintype "input"))
      (node (ref "IC2") (pin "4") (pinfunction "OUT_4") (pintype "output"))
      (node (ref "R1") (pin "1") (pinfunction "1_1") (pintype "passive"))
    )
    (net (code "43") (name "Net-(IC2A-CTRL)") (class "Default")
      (node (ref "C28") (pin "1") (pinfunction "1_1") (pintype "passive"))
      (node (ref "IC2") (pin "3") (pinfunction "CTRL_3") (pintype "input"))
      (node (ref "R30") (pin "2") (pinfunction "2_2") (pintype "passive"))
    )
    (net (code "44") (name "Net-(IC2A-IN)") (class "Default")
      (node (ref "IC2") (pin "2") (pinfunction "IN_2") (pintype "input"))
      (node (ref "R14") (pin "2") (pinfunction "2_2") (pintype "passive"))
      (node (ref "R15") (pin "2") (pinfunction "2_2") (pintype "passive"))
    )
    (net (code "45") (name "Net-(IC2B-IN)") (class "Default")
      (node (ref "IC2") (pin "7") (pinfunction "IN_7") (pintype "input"))
      (node (ref "R16") (pin "2") (pinfunction "2_2") (pintype "passive"))
      (node (ref "R17") (pin "2") (pinfunction "2_2") (pintype "passive"))
    )
    (net (code "46") (name "Net-(IC2B-OUT)") (class "Default")
      (node (ref "C12") (pin "1") (pinfunction "1_1") (pintype "passive"))
      (node (ref "IC2") (pin "5") (pinfunction "OUT_5") (pintype "output"))
      (node (ref "IC3") (pin "6") (pinfunction "-IN_6") (pintype "input"))
      (node (ref "Z5") (pin "2") (pinfunction "A_2") (pintype "bidirectional"))
    )
    (net (code "47") (name "Net-(IC2C-IN)") (class "Default")
      (node (ref "IC2") (pin "10") (pinfunction "IN_10") (pintype "input"))
      (node (ref "R4") (pin "2") (pinfunction "2_2") (pintype "passive"))
      (node (ref "R5") (pin "2") (pinfunction "2_2") (pintype "passive"))
    )
    (net (code "48") (name "Net-(IC2C-OUT)") (class "Default")
      (node (ref "C10") (pin "1") (pinfunction "1_1") (pintype "passive"))
      (node (ref "IC2") (pin "12") (pinfunction "OUT_12") (pintype "output"))
      (node (ref "IC3") (pin "9") (pinfunction "-IN_9") (pintype "input"))
    )
    (net (code "49") (name "Net-(IC2D-IN)") (class "Default")
      (node (ref "IC2") (pin "15") (pinfunction "IN_15") (pintype "input"))
      (node (ref "R2") (pin "1") (pinfunction "1_1") (pintype "passive"))
      (node (ref "R3") (pin "2") (pinfunction "2_2") (pintype "passive"))
    )
    (net (code "50") (name "Net-(IC2D-OUT)") (class "Default")
      (node (ref "IC2") (pin "13") (pinfunction "OUT_13") (pintype "output"))
      (node (ref "IC3") (pin "13") (pinfunction "-IN_13") (pintype "input"))
      (node (ref "R6") (pin "1") (pinfunction "1_1") (pintype "passive"))
    )
    (net (code "51") (name "Net-(IC3A--IN)") (class "Default")
      (node (ref "IC3") (pin "2") (pinfunction "-IN_2") (pintype "input"))
      (node (ref "R18") (pin "1") (pinfunction "1_1") (pintype "passive"))
      (node (ref "R19") (pin "1") (pinfunction "1_1") (pintype "passive"))
      (node (ref "R20") (pin "2") (pinfunction "2_2") (pintype "passive"))
      (node (ref "R21") (pin "1") (pinfunction "1_1") (pintype "passive"))
      (node (ref "R22") (pin "2") (pinfunction "2_2") (pintype "passive"))
    )
    (net (code "52") (name "Net-(IC3D-OUT)") (class "Default")
      (node (ref "IC3") (pin "14") (pinfunction "OUT_14") (pintype "output"))
      (node (ref "R19") (pin "2") (pinfunction "2_2") (pintype "passive"))
      (node (ref "R6") (pin "2") (pinfunction "2_2") (pintype "passive"))
    )
    (net (code "53") (name "Net-(IC4A-CTRL)") (class "Default")
      (node (ref "C56") (pin "1") (pinfunction "1_1") (pintype "passive"))
      (node (ref "IC4") (pin "3") (pinfunction "CTRL_3") (pintype "input"))
      (node (ref "R60") (pin "2") (pinfunction "2_2") (pintype "passive"))
    )
    (net (code "54") (name "Net-(IC4A-IN)") (class "Default")
      (node (ref "IC4") (pin "2") (pinfunction "IN_2") (pintype "input"))
      (node (ref "R44") (pin "2") (pinfunction "2_2") (pintype "passive"))
      (node (ref "R47") (pin "2") (pinfunction "2_2") (pintype "passive"))
    )
    (net (code "55") (name "Net-(IC4A-OUT)") (class "Default")
      (node (ref "C44") (pin "1") (pinfunction "1_1") (pintype "passive"))
      (node (ref "IC4") (pin "4") (pinfunction "OUT_4") (pintype "output"))
      (node (ref "IC6") (pin "6") (pinfunction "-IN_6") (pintype "input"))
      (node (ref "R52") (pin "1") (pinfunction "1_1") (pintype "passive"))
    )
    (net (code "56") (name "Net-(IC4B-IN)") (class "Default")
      (node (ref "IC4") (pin "7") (pinfunction "IN_7") (pintype "input"))
      (node (ref "R36") (pin "2") (pinfunction "2_2") (pintype "passive"))
      (node (ref "R43") (pin "2") (pinfunction "2_2") (pintype "passive"))
    )
    (net (code "57") (name "Net-(IC4B-OUT)") (class "Default")
      (node (ref "C30") (pin "1") (pinfunction "1_1") (pintype "passive"))
      (node (ref "IC4") (pin "5") (pinfunction "OUT_5") (pintype "output"))
      (node (ref "IC5") (pin "6") (pinfunction "-IN_6") (pintype "input"))
      (node (ref "Z3") (pin "2") (pinfunction "A_2") (pintype "bidirectional"))
    )
    (net (code "58") (name "Net-(IC4C-IN)") (class "Default")
      (node (ref "IC4") (pin "10") (pinfunction "IN_10") (pintype "input"))
      (node (ref "R39") (pin "2") (pinfunction "2_2") (pintype "passive"))
      (node (ref "R41") (pin "2") (pinfunction "2_2") (pintype "passive"))
    )
    (net (code "59") (name "Net-(IC4C-OUT)") (class "Default")
      (node (ref "C31") (pin "1") (pinfunction "1_1") (pintype "passive"))
      (node (ref "IC4") (pin "12") (pinfunction "OUT_12") (pintype "output"))
      (node (ref "IC5") (pin "9") (pinfunction "-IN_9") (pintype "input"))
    )
    (net (code "60") (name "Net-(IC4D-IN)") (class "Default")
      (node (ref "IC4") (pin "15") (pinfunction "IN_15") (pintype "input"))
      (node (ref "R37") (pin "1") (pinfunction "1_1") (pintype "passive"))
      (node (ref "R42") (pin "2") (pinfunction "2_2") (pintype "passive"))
    )
    (net (code "61") (name "Net-(IC4D-OUT)") (class "Default")
      (node (ref "IC4") (pin "13") (pinfunction "OUT_13") (pintype "output"))
      (node (ref "IC5") (pin "13") (pinfunction "-IN_13") (pintype "input"))
      (node (ref "R45") (pin "1") (pinfunction "1_1") (pintype "passive"))
    )
    (net (code "62") (name "Net-(IC5A--IN)") (class "Default")
      (node (ref "IC5") (pin "2") (pinfunction "-IN_2") (pintype "input"))
      (node (ref "R34") (pin "2") (pinfunction "2_2") (pintype "passive"))
      (node (ref "R35") (pin "1") (pinfunction "1_1") (pintype "passive"))
      (node (ref "R38") (pin "1") (pinfunction "1_1") (pintype "passive"))
      (node (ref "R40") (pin "1") (pinfunction "1_1") (pintype "passive"))
      (node (ref "R46") (pin "2") (pinfunction "2_2") (pintype "passive"))
    )
    (net (code "63") (name "Net-(IC5D-OUT)") (class "Default")
      (node (ref "IC5") (pin "14") (pinfunction "OUT_14") (pintype "output"))
      (node (ref "R38") (pin "2") (pinfunction "2_2") (pintype "passive"))
      (node (ref "R45") (pin "2") (pinfunction "2_2") (pintype "passive"))
    )
    (net (code "64") (name "Net-(IC6A--IN)") (class "Default")
      (node (ref "C29") (pin "1") (pinfunction "1_1") (pintype "passive"))
      (node (ref "IC6") (pin "2") (pinfunction "-IN_2") (pintype "input"))
      (node (ref "R31") (pin "1") (pinfunction "1_1") (pintype "passive"))
      (node (ref "R32") (pin "2") (pinfunction "2_2") (pintype "passive"))
      (node (ref "R57") (pin "2") (pinfunction "2_2") (pintype "passive"))
    )
    (net (code "65") (name "Net-(LED1-PadA)") (class "Default")
      (node (ref "LED1") (pin "A") (pinfunction "A_A") (pintype "passive"))
      (node (ref "R25") (pin "1") (pinfunction "1_1") (pintype "passive"))
    )
    (net (code "66") (name "Net-(LED2-PadA)") (class "Default")
      (node (ref "LED2") (pin "A") (pinfunction "A_A") (pintype "passive"))
      (node (ref "R26") (pin "1") (pinfunction "1_1") (pintype "passive"))
    )
    (net (code "67") (name "Net-(LED3-PadA)") (class "Default")
      (node (ref "LED3") (pin "A") (pinfunction "A_A") (pintype "passive"))
      (node (ref "R49") (pin "1") (pinfunction "1_1") (pintype "passive"))
    )
    (net (code "68") (name "Net-(LED4-PadA)") (class "Default")
      (node (ref "LED4") (pin "A") (pinfunction "A_A") (pintype "passive"))
      (node (ref "R50") (pin "1") (pinfunction "1_1") (pintype "passive"))
    )
    (net (code "69") (name "Net-(Q1-G)") (class "Default")
      (node (ref "Q1") (pin "1") (pinfunction "G_1") (pintype "passive"))
      (node (ref "U1") (pin "23") (pinfunction "PC0_23") (pintype "bidirectional"))
    )
    (net (code "70") (name "Net-(Q2-G)") (class "Default")
      (node (ref "Q2") (pin "1") (pinfunction "G_1") (pintype "passive"))
      (node (ref "U1") (pin "24") (pinfunction "PC1_24") (pintype "bidirectional"))
    )
    (net (code "71") (name "Net-(Q5-G)") (class "Default")
      (node (ref "Q5") (pin "1") (pinfunction "G_1") (pintype "passive"))
      (node (ref "U3") (pin "23") (pinfunction "PC0_23") (pintype "bidirectional"))
    )
    (net (code "72") (name "Net-(Q6-G)") (class "Default")
      (node (ref "Q6") (pin "1") (pinfunction "G_1") (pintype "passive"))
      (node (ref "U3") (pin "24") (pinfunction "PC1_24") (pintype "bidirectional"))
    )
    (net (code "73") (name "Net-(R23-E)") (class "Default")
      (node (ref "R10") (pin "1") (pinfunction "1_1") (pintype "passive"))
      (node (ref "R23") (pin "1") (pinfunction "E_1") (pintype "passive"))
      (node (ref "R23") (pin "2") (pinfunction "S_2") (pintype "passive"))
    )
    (net (code "74") (name "Net-(R33-E)") (class "Default")
      (node (ref "R32") (pin "1") (pinfunction "1_1") (pintype "passive"))
      (node (ref "R33") (pin "1") (pinfunction "E_1") (pintype "passive"))
      (node (ref "R33") (pin "2") (pinfunction "S_2") (pintype "passive"))
    )
    (net (code "75") (name "Net-(U1-PB6)") (class "Default")
      (node (ref "C25") (pin "2") (pinfunction "2_2") (pintype "passive"))
      (node (ref "Q3") (pin "2") (pinfunction "2_2") (pintype "passive"))
      (node (ref "U1") (pin "7") (pinfunction "PB6_7") (pintype "bidirectional"))
    )
    (net (code "76") (name "Net-(U1-PB7)") (class "Default")
      (node (ref "C26") (pin "2") (pinfunction "2_2") (pintype "passive"))
      (node (ref "Q3") (pin "1") (pinfunction "1_1") (pintype "passive"))
      (node (ref "U1") (pin "8") (pinfunction "PB7_8") (pintype "bidirectional"))
    )
    (net (code "77") (name "Net-(U1-PC4)") (class "Default")
      (node (ref "R25") (pin "2") (pinfunction "2_2") (pintype "passive"))
      (node (ref "U1") (pin "27") (pinfunction "PC4_27") (pintype "bidirectional"))
    )
    (net (code "78") (name "Net-(U1-PC5)") (class "Default")
      (node (ref "R26") (pin "2") (pinfunction "2_2") (pintype "passive"))
      (node (ref "U1") (pin "28") (pinfunction "PC5_28") (pintype "bidirectional"))
    )
    (net (code "79") (name "Net-(U1-PC6{slash}~{RESET})") (class "Default")
      (node (ref "ISP_A") (pin "5") (pinfunction "5_5") (pintype "passive"))
      (node (ref "R29") (pin "1") (pinfunction "1_1") (pintype "passive"))
      (node (ref "U1") (pin "29") (pinfunction "PC6/~{RESET}_29") (pintype "bidirectional"))
    )
    (net (code "80") (name "Net-(U2-X)") (class "Default")
      (node (ref "C20") (pin "+") (pinfunction "+_+") (pintype "passive"))
      (node (ref "U2") (pin "13") (pinfunction "X_13") (pintype "bidirectional"))
    )
    (net (code "81") (name "Net-(U3-PB6)") (class "Default")
      (node (ref "C36") (pin "2") (pinfunction "2_2") (pintype "passive"))
      (node (ref "Q4") (pin "2") (pinfunction "2_2") (pintype "passive"))
      (node (ref "U3") (pin "7") (pinfunction "PB6_7") (pintype "bidirectional"))
    )
    (net (code "82") (name "Net-(U3-PB7)") (class "Default")
      (node (ref "C37") (pin "2") (pinfunction "2_2") (pintype "passive"))
      (node (ref "Q4") (pin "1") (pinfunction "1_1") (pintype "passive"))
      (node (ref "U3") (pin "8") (pinfunction "PB7_8") (pintype "bidirectional"))
    )
    (net (code "83") (name "Net-(U3-PC4)") (class "Default")
      (node (ref "R49") (pin "2") (pinfunction "2_2") (pintype "passive"))
      (node (ref "U3") (pin "27") (pinfunction "PC4_27") (pintype "bidirectional"))
    )
    (net (code "84") (name "Net-(U3-PC5)") (class "Default")
      (node (ref "R50") (pin "2") (pinfunction "2_2") (pintype "passive"))
      (node (ref "U3") (pin "28") (pinfunction "PC5_28") (pintype "bidirectional"))
    )
    (net (code "85") (name "Net-(U3-PC6{slash}~{RESET})") (class "Default")
      (node (ref "ISP_B") (pin "5") (pinfunction "5_5") (pintype "passive"))
      (node (ref "R48") (pin "1") (pinfunction "1_1") (pintype "passive"))
      (node (ref "U3") (pin "29") (pinfunction "PC6/~{RESET}_29") (pintype "bidirectional"))
    )
    (net (code "86") (name "Net-(U4-X)") (class "Default")
      (node (ref "C48") (pin "+") (pinfunction "+_+") (pintype "passive"))
      (node (ref "U4") (pin "13") (pinfunction "X_13") (pintype "bidirectional"))
    )
    (net (code "87") (name "Net-(Z1-A)") (class "Default")
      (node (ref "R11") (pin "1") (pinfunction "1_1") (pintype "passive"))
      (node (ref "R12") (pin "2") (pinfunction "2_2") (pintype "passive"))
      (node (ref "Z1") (pin "2") (pinfunction "A_2") (pintype "bidirectional"))
    )
    (net (code "88") (name "Net-(Z2-A)") (class "Default")
      (node (ref "R56") (pin "2") (pinfunction "2_2") (pintype "passive"))
      (node (ref "R57") (pin "1") (pinfunction "1_1") (pintype "passive"))
      (node (ref "Z2") (pin "2") (pinfunction "A_2") (pintype "bidirectional"))
    )
    (net (code "89") (name "Net-(Z3-K)") (class "Default")
      (node (ref "Z3") (pin "1") (pinfunction "K_1") (pintype "bidirectional"))
      (node (ref "Z4") (pin "1") (pinfunction "K_1") (pintype "bidirectional"))
    )
    (net (code "90") (name "Net-(Z5-K)") (class "Default")
      (node (ref "Z5") (pin "1") (pinfunction "K_1") (pintype "bidirectional"))
      (node (ref "Z6") (pin "1") (pinfunction "K_1") (pintype "bidirectional"))
    )
    (net (code "91") (name "OSC") (class "Default")
      (node (ref "C21") (pin "+") (pinfunction "+_+") (pintype "passive"))
      (node (ref "U7") (pin "6") (pinfunction "~{VOUTB}_6") (pintype "input"))
    )
    (net (code "92") (name "OSC_1") (class "Default")
      (node (ref "C47") (pin "+") (pinfunction "+_+") (pintype "passive"))
      (node (ref "U$7") (pin "6") (pinfunction "~{VOUTB}_6") (pintype "input"))
    )
    (net (code "93") (name "OUT") (class "Default")
      (node (ref "C3") (pin "2") (pinfunction "2_2") (pintype "passive"))
      (node (ref "IC1") (pin "7") (pinfunction "OUT_7") (pintype "output"))
      (node (ref "R1") (pin "2") (pinfunction "2_2") (pintype "passive"))
      (node (ref "R64") (pin "2") (pinfunction "2_2") (pintype "passive"))
    )
    (net (code "94") (name "OUTA") (class "Default")
      (node (ref "JP2") (pin "6") (pinfunction "6_6") (pintype "passive"))
      (node (ref "R64") (pin "1") (pinfunction "1_1") (pintype "passive"))
    )
    (net (code "95") (name "OUTB") (class "Default")
      (node (ref "JP2") (pin "5") (pinfunction "5_5") (pintype "passive"))
      (node (ref "R62") (pin "1") (pinfunction "1_1") (pintype "passive"))
    )
    (net (code "96") (name "OUT_1") (class "Default")
      (node (ref "C44") (pin "2") (pinfunction "2_2") (pintype "passive"))
      (node (ref "IC6") (pin "7") (pinfunction "OUT_7") (pintype "output"))
      (node (ref "R52") (pin "2") (pinfunction "2_2") (pintype "passive"))
      (node (ref "R62") (pin "2") (pinfunction "2_2") (pintype "passive"))
    )
    (net (code "97") (name "RES_CONTROL") (class "Default")
      (node (ref "C14") (pin "1") (pinfunction "1_1") (pintype "passive"))
      (node (ref "IC2") (pin "14") (pinfunction "CTRL_14") (pintype "input"))
      (node (ref "R13") (pin "2") (pinfunction "2_2") (pintype "passive"))
    )
    (net (code "98") (name "RES_CONTROL_1") (class "Default")
      (node (ref "C40") (pin "1") (pinfunction "1_1") (pintype "passive"))
      (node (ref "IC4") (pin "14") (pinfunction "CTRL_14") (pintype "input"))
      (node (ref "R51") (pin "2") (pinfunction "2_2") (pintype "passive"))
    )
    (net (code "99") (name "RES_PWM") (class "Default")
      (node (ref "R13") (pin "1") (pinfunction "1_1") (pintype "passive"))
      (node (ref "U1") (pin "9") (pinfunction "PD5_9") (pintype "bidirectional"))
    )
    (net (code "100") (name "RES_PWM_1") (class "Default")
      (node (ref "R51") (pin "1") (pinfunction "1_1") (pintype "passive"))
      (node (ref "U3") (pin "9") (pinfunction "PD5_9") (pintype "bidirectional"))
    )
    (net (code "101") (name "SC") (class "Default")
      (node (ref "JP4") (pin "2") (pinfunction "2_2") (pintype "passive"))
      (node (ref "R28") (pin "1") (pinfunction "1_1") (pintype "passive"))
      (node (ref "R55") (pin "1") (pinfunction "1_1") (pintype "passive"))
    )
    (net (code "102") (name "SCK") (class "Default")
      (node (ref "ISP_A") (pin "3") (pinfunction "3_3") (pintype "passive"))
      (node (ref "R28") (pin "2") (pinfunction "2_2") (pintype "passive"))
      (node (ref "U1") (pin "17") (pinfunction "PB5_17") (pintype "bidirectional"))
    )
    (net (code "103") (name "SCK_1") (class "Default")
      (node (ref "ISP_B") (pin "3") (pinfunction "3_3") (pintype "passive"))
      (node (ref "R55") (pin "2") (pinfunction "2_2") (pintype "passive"))
      (node (ref "U3") (pin "17") (pinfunction "PB5_17") (pintype "bidirectional"))
    )
    (net (code "104") (name "SS") (class "Default")
      (node (ref "R63") (pin "2") (pinfunction "2_2") (pintype "passive"))
      (node (ref "U1") (pin "14") (pinfunction "PB2_14") (pintype "bidirectional"))
    )
    (net (code "105") (name "SSA") (class "Default")
      (node (ref "JP4") (pin "6") (pinfunction "6_6") (pintype "passive"))
      (node (ref "R63") (pin "1") (pinfunction "1_1") (pintype "passive"))
    )
    (net (code "106") (name "SSB") (class "Default")
      (node (ref "JP4") (pin "5") (pinfunction "5_5") (pintype "passive"))
      (node (ref "R61") (pin "1") (pinfunction "1_1") (pintype "passive"))
    )
    (net (code "107") (name "SS_1") (class "Default")
      (node (ref "R61") (pin "2") (pinfunction "2_2") (pintype "passive"))
      (node (ref "U3") (pin "14") (pinfunction "PB2_14") (pintype "bidirectional"))
    )
    (net (code "108") (name "VCA_CONTROL") (class "Default")
      (node (ref "R30") (pin "1") (pinfunction "1_1") (pintype "passive"))
      (node (ref "U7") (pin "8") (pinfunction "VOUTA_8") (pintype "output"))
    )
    (net (code "109") (name "VCA_CONTROL_1") (class "Default")
      (node (ref "R60") (pin "1") (pinfunction "1_1") (pintype "passive"))
      (node (ref "U$7") (pin "8") (pinfunction "VOUTA_8") (pintype "output"))
    )
    (net (code "110") (name "VCC") (class "Default")
      (node (ref "C11") (pin "+") (pinfunction "+_+") (pintype "passive"))
      (node (ref "C17") (pin "1") (pinfunction "1_1") (pintype "passive"))
      (node (ref "C2") (pin "1") (pinfunction "1_1") (pintype "passive"))
      (node (ref "C4") (pin "1") (pinfunction "1_1") (pintype "passive"))
      (node (ref "C41") (pin "1") (pinfunction "1_1") (pintype "passive"))
      (node (ref "C42") (pin "1") (pinfunction "1_1") (pintype "passive"))
      (node (ref "C43") (pin "1") (pinfunction "1_1") (pintype "passive"))
      (node (ref "C53") (pin "+") (pinfunction "+_+") (pintype "passive"))
      (node (ref "C55") (pin "1") (pinfunction "1_1") (pintype "passive"))
      (node (ref "C9") (pin "1") (pinfunction "1_1") (pintype "passive"))
      (node (ref "IC1") (pin "8") (pinfunction "V+_8") (pintype "power_in"))
      (node (ref "IC2") (pin "16") (pinfunction "V+_16") (pintype "power_in"))
      (node (ref "IC3") (pin "4") (pinfunction "V+_4") (pintype "power_in"))
      (node (ref "IC4") (pin "16") (pinfunction "V+_16") (pintype "power_in"))
      (node (ref "IC5") (pin "4") (pinfunction "V+_4") (pintype "power_in"))
      (node (ref "IC6") (pin "8") (pinfunction "V+_8") (pintype "power_in"))
      (node (ref "JP2") (pin "4") (pinfunction "4_4") (pintype "passive"))
      (node (ref "R58") (pin "2") (pinfunction "2_2") (pintype "passive"))
      (node (ref "R59") (pin "2") (pinfunction "2_2") (pintype "passive"))
      (node (ref "R7") (pin "2") (pinfunction "2_2") (pintype "passive"))
      (node (ref "R8") (pin "2") (pinfunction "2_2") (pintype "passive"))
      (node (ref "U2") (pin "16") (pinfunction "VDD_16") (pintype "input"))
      (node (ref "U4") (pin "16") (pinfunction "VDD_16") (pintype "input"))
    )
    (net (code "111") (name "VEE") (class "Default")
      (node (ref "C1") (pin "-") (pinfunction "-_-") (pintype "passive"))
      (node (ref "C13") (pin "2") (pinfunction "2_2") (pintype "passive"))
      (node (ref "C18") (pin "2") (pinfunction "2_2") (pintype "passive"))
      (node (ref "C49") (pin "2") (pinfunction "2_2") (pintype "passive"))
      (node (ref "C50") (pin "2") (pinfunction "2_2") (pintype "passive"))
      (node (ref "C51") (pin "2") (pinfunction "2_2") (pintype "passive"))
      (node (ref "C52") (pin "2") (pinfunction "2_2") (pintype "passive"))
      (node (ref "C54") (pin "-") (pinfunction "-_-") (pintype "passive"))
      (node (ref "C7") (pin "2") (pinfunction "2_2") (pintype "passive"))
      (node (ref "C8") (pin "2") (pinfunction "2_2") (pintype "passive"))
      (node (ref "IC1") (pin "4") (pinfunction "V-_4") (pintype "power_in"))
      (node (ref "IC2") (pin "9") (pinfunction "V-_9") (pintype "power_in"))
      (node (ref "IC3") (pin "11") (pinfunction "V-_11") (pintype "power_in"))
      (node (ref "IC4") (pin "9") (pinfunction "V-_9") (pintype "power_in"))
      (node (ref "IC5") (pin "11") (pinfunction "V-_11") (pintype "power_in"))
      (node (ref "IC6") (pin "4") (pinfunction "V-_4") (pintype "power_in"))
      (node (ref "JP2") (pin "2") (pinfunction "2_2") (pintype "passive"))
      (node (ref "R12") (pin "1") (pinfunction "1_1") (pintype "passive"))
      (node (ref "R56") (pin "1") (pinfunction "1_1") (pintype "passive"))
      (node (ref "U2") (pin "7") (pinfunction "VEE_7") (pintype "power_in"))
      (node (ref "U4") (pin "7") (pinfunction "VEE_7") (pintype "power_in"))
    )
    (net (code "112") (name "unconnected-(IC2E-MODE-Pad1)") (class "Default")
      (node (ref "IC2") (pin "1") (pinfunction "MODE_1") (pintype "input"))
    )
    (net (code "113") (name "unconnected-(IC4E-MODE-Pad1)") (class "Default")
      (node (ref "IC4") (pin "1") (pinfunction "MODE_1") (pintype "input"))
    )
    (net (code "114") (name "unconnected-(U1-ADC6-Pad19)") (class "Default")
      (node (ref "U1") (pin "19") (pinfunction "ADC6_19") (pintype "bidirectional"))
    )
    (net (code "115") (name "unconnected-(U1-ADC7-Pad22)") (class "Default")
      (node (ref "U1") (pin "22") (pinfunction "ADC7_22") (pintype "bidirectional"))
    )
    (net (code "116") (name "unconnected-(U1-AREF-Pad20)") (class "Default")
      (node (ref "U1") (pin "20") (pinfunction "AREF_20") (pintype "input"))
    )
    (net (code "117") (name "unconnected-(U1-PB1-Pad13)") (class "Default")
      (node (ref "U1") (pin "13") (pinfunction "PB1_13") (pintype "bidirectional"))
    )
    (net (code "118") (name "unconnected-(U1-PC2-Pad25)") (class "Default")
      (node (ref "U1") (pin "25") (pinfunction "PC2_25") (pintype "bidirectional"))
    )
    (net (code "119") (name "unconnected-(U1-PC3-Pad26)") (class "Default")
      (node (ref "U1") (pin "26") (pinfunction "PC3_26") (pintype "bidirectional"))
    )
    (net (code "120") (name "unconnected-(U1-PD0-Pad30)") (class "Default")
      (node (ref "U1") (pin "30") (pinfunction "PD0_30") (pintype "bidirectional"))
    )
    (net (code "121") (name "unconnected-(U1-PD3-Pad1)") (class "Default")
      (node (ref "U1") (pin "1") (pinfunction "PD3_1") (pintype "bidirectional"))
    )
    (net (code "122") (name "unconnected-(U1-PD7-Pad11)") (class "Default")
      (node (ref "U1") (pin "11") (pinfunction "PD7_11") (pintype "bidirectional"))
    )
    (net (code "123") (name "unconnected-(U2-Y-Pad3)") (class "Default")
      (node (ref "U2") (pin "3") (pinfunction "Y_3") (pintype "bidirectional"))
    )
    (net (code "124") (name "unconnected-(U3-ADC6-Pad19)") (class "Default")
      (node (ref "U3") (pin "19") (pinfunction "ADC6_19") (pintype "bidirectional"))
    )
    (net (code "125") (name "unconnected-(U3-ADC7-Pad22)") (class "Default")
      (node (ref "U3") (pin "22") (pinfunction "ADC7_22") (pintype "bidirectional"))
    )
    (net (code "126") (name "unconnected-(U3-AREF-Pad20)") (class "Default")
      (node (ref "U3") (pin "20") (pinfunction "AREF_20") (pintype "input"))
    )
    (net (code "127") (name "unconnected-(U3-PB1-Pad13)") (class "Default")
      (node (ref "U3") (pin "13") (pinfunction "PB1_13") (pintype "bidirectional"))
    )
    (net (code "128") (name "unconnected-(U3-PC2-Pad25)") (class "Default")
      (node (ref "U3") (pin "25") (pinfunction "PC2_25") (pintype "bidirectional"))
    )
    (net (code "129") (name "unconnected-(U3-PC3-Pad26)") (class "Default")
      (node (ref "U3") (pin "26") (pinfunction "PC3_26") (pintype "bidirectional"))
    )
    (net (code "130") (name "unconnected-(U3-PD0-Pad30)") (class "Default")
      (node (ref "U3") (pin "30") (pinfunction "PD0_30") (pintype "bidirectional"))
    )
    (net (code "131") (name "unconnected-(U3-PD3-Pad1)") (class "Default")
      (node (ref "U3") (pin "1") (pinfunction "PD3_1") (pintype "bidirectional"))
    )
    (net (code "132") (name "unconnected-(U3-PD7-Pad11)") (class "Default")
      (node (ref "U3") (pin "11") (pinfunction "PD7_11") (pintype "bidirectional"))
    )
    (net (code "133") (name "unconnected-(U4-Y-Pad3)") (class "Default")
      (node (ref "U4") (pin "3") (pinfunction "Y_3") (pintype "bidirectional"))
    )
  )
)
